# Main.net
KiCad netlist of a schematic drawn in Altium Designer
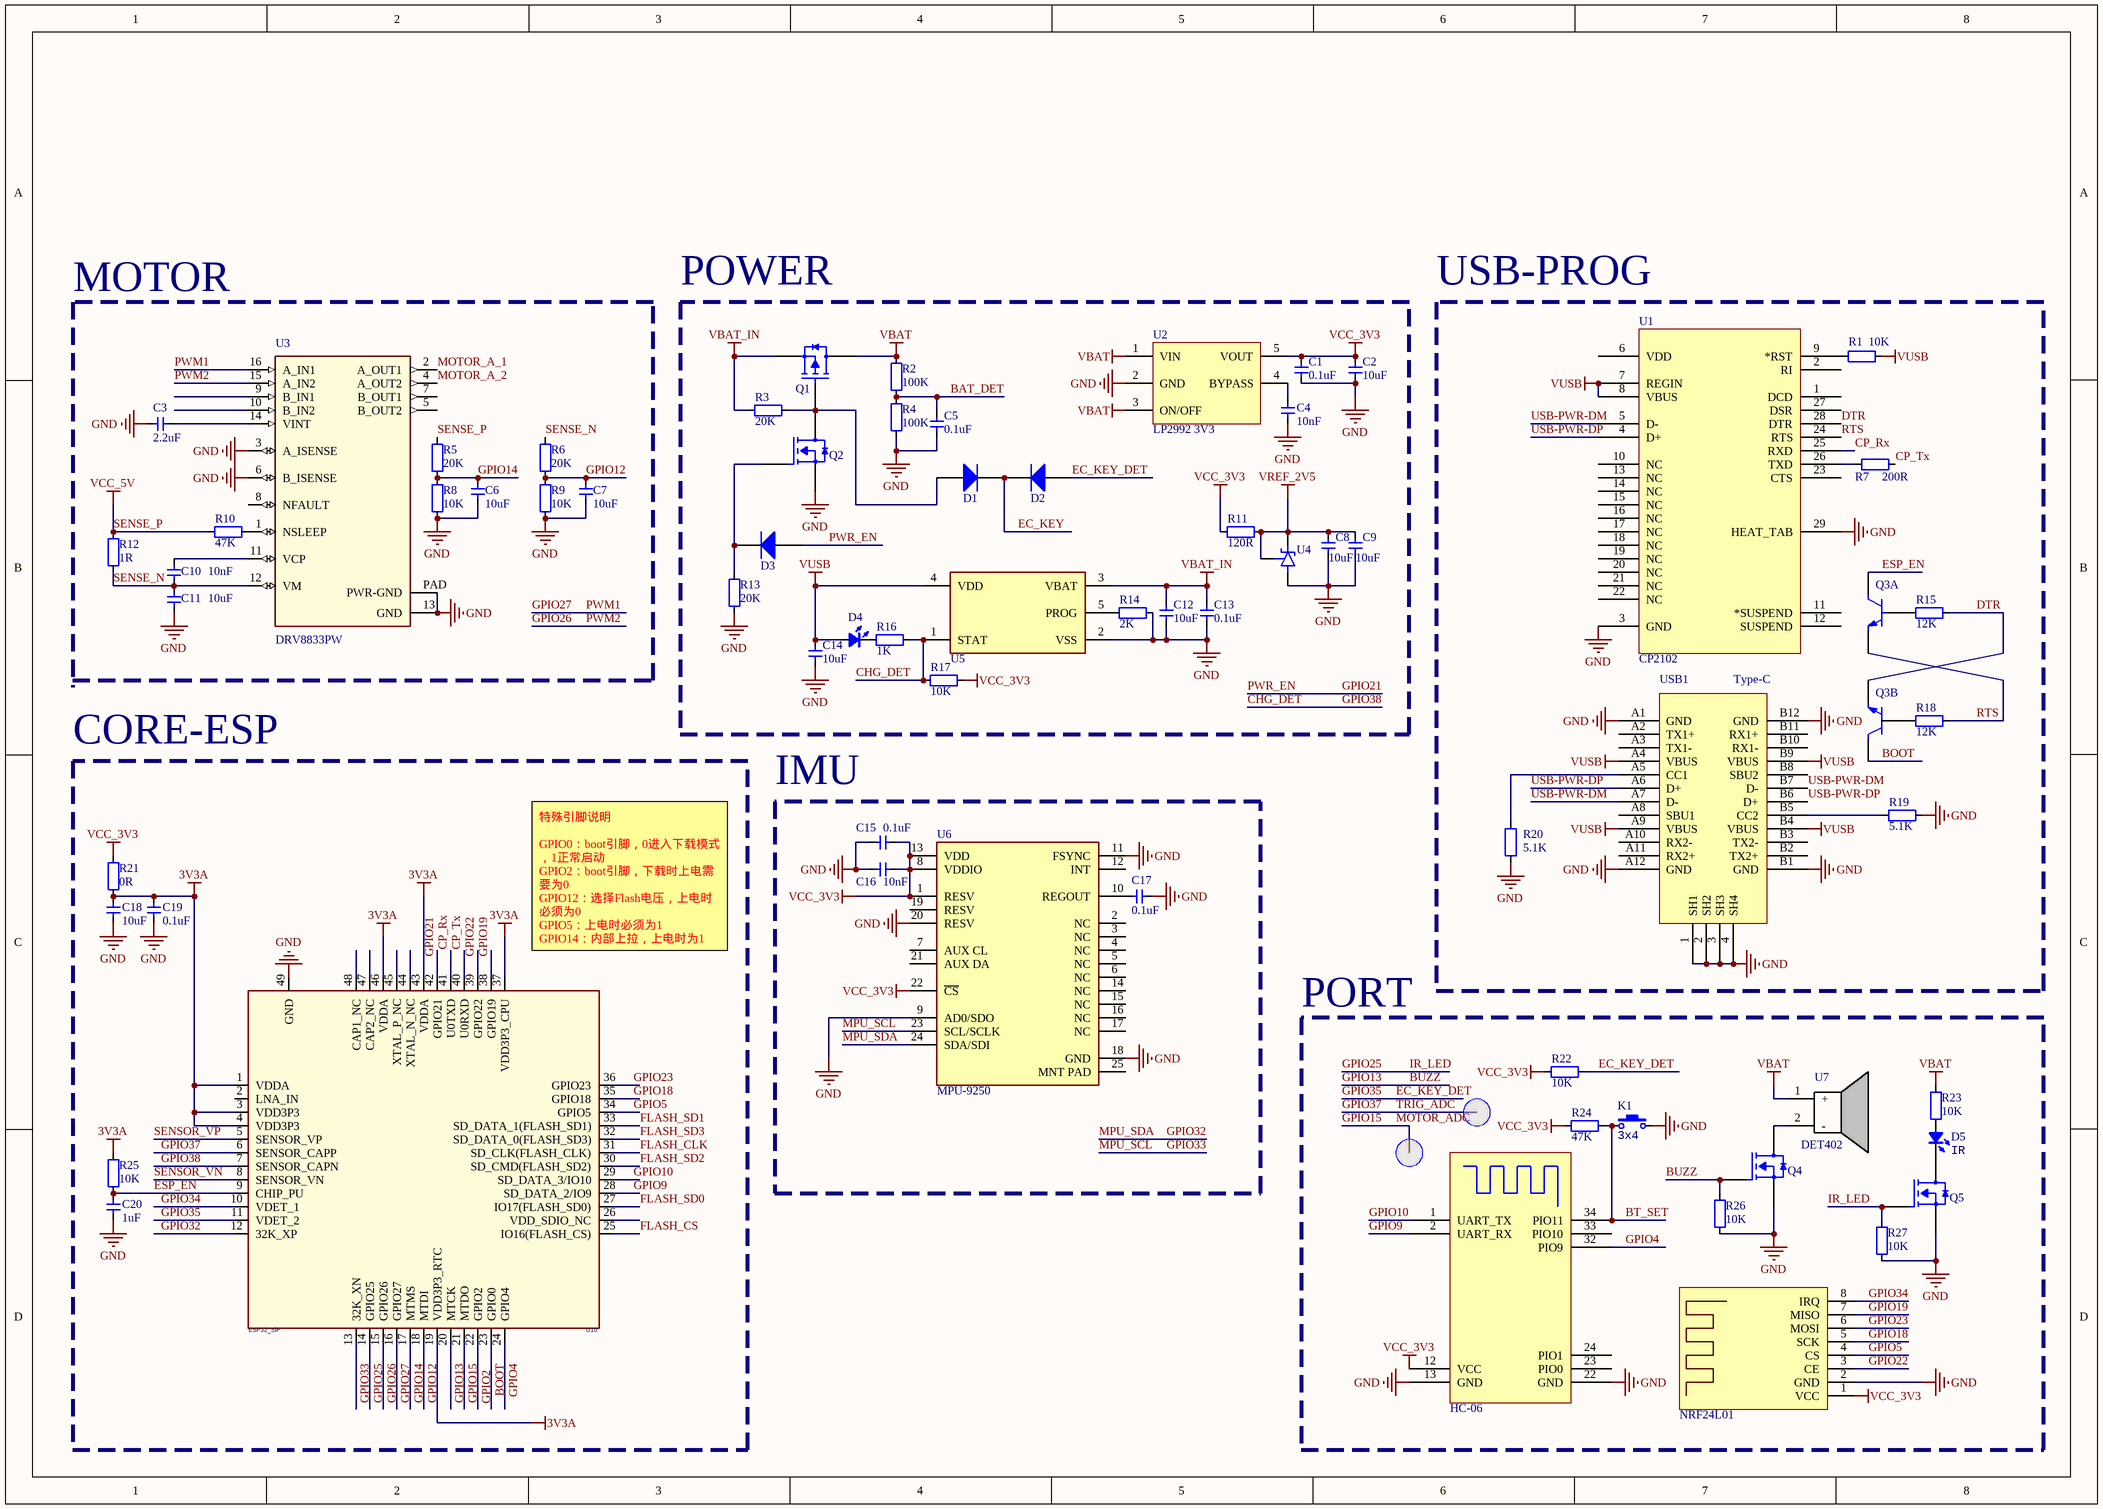
[diagram p0: Main.SchDoc]

(export (version "E")
  (design (tool "Eeschema 10.0.6"))
  (components
    (comp (ref "C1")
      (value "0.1uF")
      (footprint "CAP_0402")
      (description "Capacitor")
      (libsource (lib "MyPcbLib") (part "电容-0402"))
    )
    (comp (ref "C2")
      (value "10uF")
      (footprint "CAP_0402")
      (description "Capacitor")
      (libsource (lib "MyPcbLib") (part "电容-0402"))
    )
    (comp (ref "C3")
      (value "2.2uF")
      (footprint "CAP_0402")
      (description "Capacitor")
      (libsource (lib "MyPcbLib") (part "电容-0402"))
    )
    (comp (ref "C4")
      (value "10nF")
      (footprint "CAP_0402")
      (description "Capacitor")
      (libsource (lib "MyPcbLib") (part "电容-0402"))
    )
    (comp (ref "C5")
      (value "0.1uF")
      (footprint "CAP_0402")
      (description "Capacitor")
      (libsource (lib "MyPcbLib") (part "电容-0402"))
    )
    (comp (ref "C6")
      (value "10uF")
      (footprint "CAP_0402")
      (description "Capacitor")
      (libsource (lib "MyPcbLib") (part "电容-0402"))
    )
    (comp (ref "C7")
      (value "10uF")
      (footprint "CAP_0402")
      (description "Capacitor")
      (libsource (lib "MyPcbLib") (part "电容-0402"))
    )
    (comp (ref "C8")
      (value "10uF")
      (footprint "CAP_0402")
      (description "Capacitor")
      (libsource (lib "MyPcbLib") (part "电容-0402"))
    )
    (comp (ref "C9")
      (value "10uF")
      (footprint "CAP_0402")
      (description "Capacitor")
      (libsource (lib "MyPcbLib") (part "电容-0402"))
    )
    (comp (ref "C10")
      (value "10nF")
      (footprint "CAP_0402")
      (description "Capacitor")
      (libsource (lib "MyPcbLib") (part "电容-0402"))
    )
    (comp (ref "C11")
      (value "10uF")
      (footprint "CAP_0402")
      (description "Capacitor")
      (libsource (lib "MyPcbLib") (part "电容-0402"))
    )
    (comp (ref "C12")
      (value "10uF")
      (footprint "CAP_0402")
      (description "Capacitor")
      (libsource (lib "MyPcbLib") (part "电容-0402"))
    )
    (comp (ref "C13")
      (value "0.1uF")
      (footprint "CAP_0402")
      (description "Capacitor")
      (libsource (lib "MyPcbLib") (part "电容-0402"))
    )
    (comp (ref "C14")
      (value "10uF")
      (footprint "CAP_0402")
      (description "Capacitor")
      (libsource (lib "MyPcbLib") (part "电容-0402"))
    )
    (comp (ref "C15")
      (value "0.1uF")
      (footprint "CAP_0402")
      (description "Capacitor")
      (libsource (lib "MyPcbLib") (part "电容-0402"))
    )
    (comp (ref "C16")
      (value "10nF")
      (footprint "CAP_0402")
      (description "Capacitor")
      (libsource (lib "MyPcbLib") (part "电容-0402"))
    )
    (comp (ref "C17")
      (value "0.1uF")
      (footprint "CAP_0402")
      (description "Capacitor")
      (libsource (lib "MyPcbLib") (part "电容-0402"))
    )
    (comp (ref "C18")
      (value "10uF")
      (footprint "CAP_0402")
      (description "Capacitor")
      (libsource (lib "MyPcbLib") (part "电容-0402"))
    )
    (comp (ref "C19")
      (value "0.1uF")
      (footprint "CAP_0402")
      (description "Capacitor")
      (libsource (lib "MyPcbLib") (part "电容-0402"))
    )
    (comp (ref "C20")
      (value "1uF")
      (footprint "CAP_0402")
      (description "Capacitor")
      (libsource (lib "MyPcbLib") (part "电容-0402"))
    )
    (comp (ref "D1")
      (value "二极管-5819W")
      (footprint "SOD-323")
      (description "40V")
      (libsource (lib "MyPcbLib") (part "二极管-5819W"))
    )
    (comp (ref "D2")
      (value "二极管-5819W")
      (footprint "SOD-323")
      (description "40V")
      (libsource (lib "MyPcbLib") (part "二极管-5819W"))
    )
    (comp (ref "D3")
      (value "二极管-5819W")
      (footprint "SOD-323")
      (description "40V")
      (libsource (lib "MyPcbLib") (part "二极管-5819W"))
    )
    (comp (ref "D4")
      (value "color?")
      (footprint "LED_0402_RED")
      (description "LED")
      (libsource (lib "KitSprout") (part "LED_0402"))
    )
    (comp (ref "D5")
      (value "color?")
      (footprint "LED_0805_RED")
      (description "LED")
      (fields (field (name "TYPE") "IR"))
      (libsource (lib "KitSprout") (part "LED_0805"))
    )
    (comp (ref "K1")
      (value "3x4")
      (footprint "ButtonTACT_3x4x2_180")
      (description "Button")
      (fields (field (name "Comment") "TACT 2P"))
      (libsource (lib "KitSprout") (part "ButtonTACT_3x4x2_180"))
    )
    (comp (ref "Q1")
      (value "AO3401A")
      (footprint "SOT23-3")
      (description "P-MOS")
      (libsource (lib "MyPcbLib") (part "AO3401A"))
    )
    (comp (ref "Q2")
      (value "AO3400A")
      (footprint "SOT23-3")
      (description "N-MOS")
      (libsource (lib "MyPcbLib") (part "AO3400A"))
    )
    (comp (ref "Q3")
      (value "BC847BVC-7")
      (footprint "SOT563-6")
      (libsource (lib "MyPcbLib") (part "BC847BVC-7"))
    )
    (comp (ref "Q4")
      (value "AO3400A")
      (footprint "SOT23-3")
      (description "N-MOS")
      (libsource (lib "MyPcbLib") (part "AO3400A"))
    )
    (comp (ref "Q5")
      (value "AO3400A")
      (footprint "SOT23-3")
      (description "N-MOS")
      (libsource (lib "MyPcbLib") (part "AO3400A"))
    )
    (comp (ref "R1")
      (value "10K")
      (footprint "RES_0402")
      (description "Resistor")
      (libsource (lib "") (part "电阻-0402_3"))
    )
    (comp (ref "R2")
      (value "100K")
      (footprint "RES_0402")
      (description "Resistor")
      (libsource (lib "MyPcbLib") (part "电阻-0402"))
    )
    (comp (ref "R3")
      (value "20K")
      (footprint "RES_0402")
      (description "Resistor")
      (libsource (lib "") (part "电阻-0402_1"))
    )
    (comp (ref "R4")
      (value "100K")
      (footprint "RES_0402")
      (description "Resistor")
      (libsource (lib "MyPcbLib") (part "电阻-0402"))
    )
    (comp (ref "R5")
      (value "20K")
      (footprint "RES_0402")
      (description "Resistor")
      (libsource (lib "MyPcbLib") (part "电阻-0402"))
    )
    (comp (ref "R6")
      (value "20K")
      (footprint "RES_0402")
      (description "Resistor")
      (libsource (lib "MyPcbLib") (part "电阻-0402"))
    )
    (comp (ref "R7")
      (value "200R")
      (footprint "RES_0402")
      (description "Resistor")
      (libsource (lib "") (part "电阻-0402_3"))
    )
    (comp (ref "R8")
      (value "10K")
      (footprint "RES_0402")
      (description "Resistor")
      (libsource (lib "MyPcbLib") (part "电阻-0402"))
    )
    (comp (ref "R9")
      (value "10K")
      (footprint "RES_0402")
      (description "Resistor")
      (libsource (lib "MyPcbLib") (part "电阻-0402"))
    )
    (comp (ref "R10")
      (value "47K")
      (footprint "RES_0402")
      (description "Resistor")
      (libsource (lib "") (part "电阻-0402_3"))
    )
    (comp (ref "R11")
      (value "120R")
      (footprint "RES_0402")
      (description "Resistor")
      (libsource (lib "") (part "电阻-0402_1"))
    )
    (comp (ref "R12")
      (value "1R")
      (footprint "1206-RES")
      (description "Resistor")
      (libsource (lib "MyPcbLib") (part "电阻-1206"))
    )
    (comp (ref "R13")
      (value "20K")
      (footprint "RES_0402")
      (description "Resistor")
      (libsource (lib "MyPcbLib") (part "电阻-0402"))
    )
    (comp (ref "R14")
      (value "2K")
      (footprint "RES_0402")
      (description "Resistor")
      (libsource (lib "") (part "电阻-0402_1"))
    )
    (comp (ref "R15")
      (value "12K")
      (footprint "RES_0402")
      (description "Resistor")
      (libsource (lib "") (part "电阻-0402_3"))
    )
    (comp (ref "R16")
      (value "1K")
      (footprint "RES_0402")
      (description "Resistor")
      (libsource (lib "") (part "电阻-0402_1"))
    )
    (comp (ref "R17")
      (value "10K")
      (footprint "RES_0402")
      (description "Resistor")
      (libsource (lib "") (part "电阻-0402_1"))
    )
    (comp (ref "R18")
      (value "12K")
      (footprint "RES_0402")
      (description "Resistor")
      (libsource (lib "") (part "电阻-0402_3"))
    )
    (comp (ref "R19")
      (value "5.1K")
      (footprint "RES_0402")
      (description "Resistor")
      (libsource (lib "") (part "电阻-0402_3"))
    )
    (comp (ref "R20")
      (value "5.1K")
      (footprint "RES_0402")
      (description "Resistor")
      (libsource (lib "") (part "电阻-0402_2"))
    )
    (comp (ref "R21")
      (value "0R")
      (footprint "RES_0402")
      (description "Resistor")
      (libsource (lib "") (part "电阻-0402_2"))
    )
    (comp (ref "R22")
      (value "10K")
      (footprint "RES_0402")
      (description "Resistor")
      (libsource (lib "") (part "电阻-0402_1"))
    )
    (comp (ref "R23")
      (value "10K")
      (footprint "RES_0402")
      (description "Resistor")
      (libsource (lib "MyPcbLib") (part "电阻-0402"))
    )
    (comp (ref "R24")
      (value "47K")
      (footprint "RES_0402")
      (description "Resistor")
      (libsource (lib "") (part "电阻-0402_1"))
    )
    (comp (ref "R25")
      (value "10K")
      (footprint "RES_0402")
      (description "Resistor")
      (libsource (lib "") (part "电阻-0402_2"))
    )
    (comp (ref "R26")
      (value "10K")
      (footprint "RES_0402")
      (description "Resistor")
      (libsource (lib "MyPcbLib") (part "电阻-0402"))
    )
    (comp (ref "R27")
      (value "10K")
      (footprint "RES_0402")
      (description "Resistor")
      (libsource (lib "MyPcbLib") (part "电阻-0402"))
    )
    (comp (ref "T1") (value "测试点") (footprint "TEST_PT") (libsource (lib "MyPcbLib") (part "测试点")))
    (comp (ref "T2") (value "测试点") (footprint "TEST_PT") (libsource (lib "MyPcbLib") (part "测试点")))
    (comp (ref "U1")
      (value "CP2102")
      (footprint "QFN-28")
      (description "USB转TTL")
      (libsource (lib "mLib") (part "CP2102"))
    )
    (comp (ref "U2")
      (value "LP2992 3V3")
      (footprint "SOT23-5")
      (description "LDO")
      (libsource (lib "mLib") (part "LP2992"))
    )
    (comp (ref "U3") (value "DRV8833PW") (footprint "TSSOP-16") (libsource (lib "mLib") (part "DRV8833PW")))
    (comp (ref "U4")
      (value "TL431IDBZT")
      (footprint "SOT23-3")
      (description "Adjustable precision shunt regulator 3-SOT-23 -40 to 85")
      (fields (field (name "MF") "Texas Instruments"))
      (libsource (lib "MyPcbLib") (part "TL431IDBZT"))
    )
    (comp (ref "U5")
      (value "MCP73831T")
      (footprint "SOT23-5")
      (libsource (lib "MyPcbLib") (part "MCP73831T"))
    )
    (comp (ref "U6")
      (value "MPU9250")
      (footprint "QFN-24-3x3")
      (description "IC IMU ACCEL/GYRO/MAG I2C/SPI 24QFN")
      (fields
        (field (name "MANUFACTURER") "TDK InvenSense")
        (field (name "MOUSER PART NUMBER") "410-MPU-9250")
        (field (name "PART NUMBER") "MPU-9250")
      )
      (libsource (lib "MyPcbLib") (part "MPU9250"))
    )
    (comp (ref "U7") (value "DET402") (footprint "DET402") (libsource (lib "MyPcbLib") (part "DET402")))
    (comp (ref "U8") (value "HC-06") (footprint "蓝牙模块HC-06") (libsource (lib "MyPcbLib") (part "蓝牙模块HC-06")))
    (comp (ref "U9")
      (value "NRF24L01")
      (footprint "NRF24L01-MODULE")
      (libsource (lib "MyPcbLib") (part "NRF24L01模块"))
    )
    (comp (ref "U10")
      (value "ESP32_SIP")
      (footprint "QFN-48_7X7")
      (libsource (lib "mLib") (part "ESP32-PICO"))
    )
    (comp (ref "USB1")
      (value "Type-C")
      (footprint "Type-C-TOP")
      (libsource (lib "MyPcbLib") (part "USB-Type-C-TOP"))
    )
  )
  (nets
    (net (code "1") (name "/BAT_DET") (class "Default")
      (node (ref "C5") (pin "2") (pinfunction "2_2") (pintype "passive"))
      (node (ref "R2") (pin "1") (pinfunction "1_1") (pintype "passive"))
      (node (ref "R4") (pin "2") (pinfunction "2_2") (pintype "passive"))
    )
    (net (code "2") (name "/BOOT") (class "Default")
      (node (ref "Q3") (pin "3") (pinfunction "C2_3") (pintype "passive"))
      (node (ref "U10") (pin "23") (pinfunction "GPIO0_23") (pintype "passive"))
    )
    (net (code "3") (name "/BT_SET") (class "Default")
      (node (ref "K1") (pin "1") (pinfunction "1_1") (pintype "passive"))
      (node (ref "R24") (pin "2") (pinfunction "2_2") (pintype "passive"))
      (node (ref "U8") (pin "34") (pinfunction "PIO11_34") (pintype "passive"))
    )
    (net (code "4") (name "/BUZZ") (class "Default")
      (node (ref "Q4") (pin "1") (pinfunction "G_1") (pintype "passive"))
      (node (ref "R26") (pin "2") (pinfunction "2_2") (pintype "passive"))
      (node (ref "U10") (pin "20") (pinfunction "MTCK_20") (pintype "passive"))
    )
    (net (code "5") (name "/CHG_DET") (class "Default")
      (node (ref "R16") (pin "2") (pinfunction "2_2") (pintype "passive"))
      (node (ref "R17") (pin "1") (pinfunction "1_1") (pintype "passive"))
      (node (ref "U10") (pin "7") (pinfunction "SENSOR_CAPN_7") (pintype "passive"))
      (node (ref "U5") (pin "1") (pinfunction "STAT_1") (pintype "passive"))
    )
    (net (code "6") (name "/CP_Rx") (class "Default")
      (node (ref "U1") (pin "25") (pinfunction "RXD_25") (pintype "passive"))
      (node (ref "U10") (pin "41") (pinfunction "U0TXD_41") (pintype "power_in"))
    )
    (net (code "7") (name "/CP_Tx") (class "Default")
      (node (ref "R7") (pin "1") (pinfunction "1_1") (pintype "passive"))
      (node (ref "U10") (pin "40") (pinfunction "U0RXD_40") (pintype "power_in"))
    )
    (net (code "8") (name "/DTR") (class "Default")
      (node (ref "Q3") (pin "4") (pinfunction "E2_4") (pintype "passive"))
      (node (ref "R15") (pin "1") (pinfunction "1_1") (pintype "passive"))
      (node (ref "U1") (pin "28") (pinfunction "DTR_28") (pintype "passive"))
    )
    (net (code "9") (name "/EC_KEY") (class "Default")
      (node (ref "D1") (pin "2") (pinfunction "K_2") (pintype "passive"))
      (node (ref "D2") (pin "2") (pinfunction "K_2") (pintype "passive"))
    )
    (net (code "10") (name "/EC_KEY_DET") (class "Default")
      (node (ref "D2") (pin "1") (pinfunction "A_1") (pintype "passive"))
      (node (ref "R22") (pin "2") (pinfunction "2_2") (pintype "passive"))
      (node (ref "U10") (pin "11") (pinfunction "VDET_2_11") (pintype "passive"))
    )
    (net (code "11") (name "/ESP_EN") (class "Default")
      (node (ref "C20") (pin "1") (pinfunction "1_1") (pintype "passive"))
      (node (ref "Q3") (pin "6") (pinfunction "C1_6") (pintype "passive"))
      (node (ref "R25") (pin "2") (pinfunction "2_2") (pintype "passive"))
      (node (ref "U10") (pin "9") (pinfunction "CHIP_PU_9") (pintype "passive"))
    )
    (net (code "12") (name "/FLASH_CLK") (class "Default")
      (node (ref "U10") (pin "31") (pinfunction "SD_CLK(FLASH_CLK)_31") (pintype "passive"))
    )
    (net (code "13") (name "/FLASH_CS") (class "Default")
      (node (ref "U10") (pin "25") (pinfunction "IO16(FLASH_CS)_25") (pintype "passive"))
    )
    (net (code "14") (name "/FLASH_SD0") (class "Default")
      (node (ref "U10") (pin "27") (pinfunction "IO17(FLASH_SD0)_27") (pintype "passive"))
    )
    (net (code "15") (name "/FLASH_SD1") (class "Default")
      (node (ref "U10") (pin "33") (pinfunction "SD_DATA_1(FLASH_SD1)_33") (pintype "passive"))
    )
    (net (code "16") (name "/FLASH_SD2") (class "Default")
      (node (ref "U10") (pin "30") (pinfunction "SD_CMD(FLASH_SD2)_30") (pintype "passive"))
    )
    (net (code "17") (name "/FLASH_SD3") (class "Default")
      (node (ref "U10") (pin "32") (pinfunction "SD_DATA_0(FLASH_SD3)_32") (pintype "passive"))
    )
    (net (code "18") (name "/GPIO2") (class "Default")
      (node (ref "U10") (pin "22") (pinfunction "GPIO2_22") (pintype "passive"))
    )
    (net (code "19") (name "/GPIO4") (class "Default")
      (node (ref "U10") (pin "24") (pinfunction "GPIO4_24") (pintype "passive"))
      (node (ref "U8") (pin "32") (pinfunction "PIO9_32") (pintype "passive"))
    )
    (net (code "20") (name "/GPIO5") (class "Default")
      (node (ref "U10") (pin "34") (pinfunction "GPIO5_34") (pintype "passive"))
      (node (ref "U9") (pin "4") (pinfunction "CS_4") (pintype "passive"))
    )
    (net (code "21") (name "/GPIO9") (class "Default")
      (node (ref "U10") (pin "28") (pinfunction "SD_DATA_2/IO9_28") (pintype "passive"))
      (node (ref "U8") (pin "2") (pinfunction "UART_RX_2") (pintype "passive"))
    )
    (net (code "22") (name "/GPIO10") (class "Default")
      (node (ref "U10") (pin "29") (pinfunction "SD_DATA_3/IO10_29") (pintype "passive"))
      (node (ref "U8") (pin "1") (pinfunction "UART_TX_1") (pintype "passive"))
    )
    (net (code "23") (name "/GPIO12") (class "Default")
      (node (ref "C7") (pin "2") (pinfunction "2_2") (pintype "passive"))
      (node (ref "R6") (pin "1") (pinfunction "1_1") (pintype "passive"))
      (node (ref "R9") (pin "2") (pinfunction "2_2") (pintype "passive"))
      (node (ref "U10") (pin "18") (pinfunction "MTDI_18") (pintype "passive"))
    )
    (net (code "24") (name "/GPIO14") (class "Default")
      (node (ref "C6") (pin "2") (pinfunction "2_2") (pintype "passive"))
      (node (ref "R5") (pin "1") (pinfunction "1_1") (pintype "passive"))
      (node (ref "R8") (pin "2") (pinfunction "2_2") (pintype "passive"))
      (node (ref "U10") (pin "17") (pinfunction "MTMS_17") (pintype "passive"))
    )
    (net (code "25") (name "/GPIO15") (class "Default")
      (node (ref "T2") (pin "0") (pinfunction "0_0") (pintype "passive"))
      (node (ref "U10") (pin "21") (pinfunction "MTDO_21") (pintype "passive"))
    )
    (net (code "26") (name "/GPIO18") (class "Default")
      (node (ref "U10") (pin "35") (pinfunction "GPIO18_35") (pintype "passive"))
      (node (ref "U9") (pin "5") (pinfunction "SCK_5") (pintype "passive"))
    )
    (net (code "27") (name "/GPIO19") (class "Default")
      (node (ref "U10") (pin "38") (pinfunction "GPIO19_38") (pintype "passive"))
      (node (ref "U9") (pin "7") (pinfunction "MISO_7") (pintype "passive"))
    )
    (net (code "28") (name "/GPIO21") (class "Default")
      (node (ref "D3") (pin "1") (pinfunction "A_1") (pintype "passive"))
      (node (ref "U10") (pin "42") (pinfunction "GPIO21_42") (pintype "passive"))
    )
    (net (code "29") (name "/GPIO22") (class "Default")
      (node (ref "U10") (pin "39") (pinfunction "GPIO22_39") (pintype "passive"))
      (node (ref "U9") (pin "3") (pinfunction "CE_3") (pintype "passive"))
    )
    (net (code "30") (name "/GPIO23") (class "Default")
      (node (ref "U10") (pin "36") (pinfunction "GPIO23_36") (pintype "passive"))
      (node (ref "U9") (pin "6") (pinfunction "MOSI_6") (pintype "passive"))
    )
    (net (code "31") (name "/GPIO25") (class "Default")
      (node (ref "Q5") (pin "1") (pinfunction "G_1") (pintype "passive"))
      (node (ref "R27") (pin "2") (pinfunction "2_2") (pintype "passive"))
      (node (ref "U10") (pin "14") (pinfunction "GPIO25_14") (pintype "passive"))
    )
    (net (code "32") (name "/GPIO26") (class "Default")
      (node (ref "U10") (pin "15") (pinfunction "GPIO26_15") (pintype "passive"))
      (node (ref "U3") (pin "15") (pinfunction "A_IN2_15") (pintype "input"))
    )
    (net (code "33") (name "/GPIO27") (class "Default")
      (node (ref "U10") (pin "16") (pinfunction "GPIO27_16") (pintype "passive"))
      (node (ref "U3") (pin "16") (pinfunction "A_IN1_16") (pintype "input"))
    )
    (net (code "34") (name "/GPIO32") (class "Default")
      (node (ref "U10") (pin "12") (pinfunction "32K_XP_12") (pintype "passive"))
      (node (ref "U6") (pin "24") (pinfunction "SDA/SDI_24") (pintype "passive"))
    )
    (net (code "35") (name "/GPIO33") (class "Default")
      (node (ref "U10") (pin "13") (pinfunction "32K_XN_13") (pintype "passive"))
      (node (ref "U6") (pin "23") (pinfunction "SCL/SCLK_23") (pintype "passive"))
    )
    (net (code "36") (name "/GPIO34") (class "Default")
      (node (ref "U10") (pin "10") (pinfunction "VDET_1_10") (pintype "passive"))
      (node (ref "U9") (pin "8") (pinfunction "IRQ_8") (pintype "passive"))
    )
    (net (code "37") (name "/GPIO37") (class "Default")
      (node (ref "T1") (pin "0") (pinfunction "0_0") (pintype "passive"))
      (node (ref "U10") (pin "6") (pinfunction "SENSOR_CAPP_6") (pintype "passive"))
    )
    (net (code "38") (name "/MOTOR_A_1") (class "Default")
      (node (ref "U3") (pin "2") (pinfunction "A_OUT1_2") (pintype "output"))
    )
    (net (code "39") (name "/MOTOR_A_2") (class "Default")
      (node (ref "U3") (pin "4") (pinfunction "A_OUT2_4") (pintype "output"))
    )
    (net (code "40") (name "/RTS") (class "Default")
      (node (ref "Q3") (pin "1") (pinfunction "E1_1") (pintype "passive"))
      (node (ref "R18") (pin "1") (pinfunction "1_1") (pintype "passive"))
      (node (ref "U1") (pin "24") (pinfunction "RTS_24") (pintype "passive"))
    )
    (net (code "41") (name "/SENSE_N") (class "Default")
      (node (ref "C10") (pin "1") (pinfunction "1_1") (pintype "passive"))
      (node (ref "C11") (pin "2") (pinfunction "2_2") (pintype "passive"))
      (node (ref "R12") (pin "1") (pinfunction "1_1") (pintype "passive"))
      (node (ref "R6") (pin "2") (pinfunction "2_2") (pintype "passive"))
      (node (ref "U3") (pin "12") (pinfunction "VM_12") (pintype "bidirectional"))
    )
    (net (code "42") (name "/SENSOR_VN") (class "Default")
      (node (ref "U10") (pin "8") (pinfunction "SENSOR_VN_8") (pintype "passive"))
    )
    (net (code "43") (name "/SENSOR_VP") (class "Default")
      (node (ref "U10") (pin "5") (pinfunction "SENSOR_VP_5") (pintype "passive"))
    )
    (net (code "44") (name "/USB-PWR-DM") (class "Default")
      (node (ref "U1") (pin "5") (pinfunction "D-_5") (pintype "passive"))
      (node (ref "USB1") (pin "A7") (pinfunction "D-_A7") (pintype "passive"))
      (node (ref "USB1") (pin "B7") (pinfunction "D-_B7") (pintype "passive"))
    )
    (net (code "45") (name "/USB-PWR-DP") (class "Default")
      (node (ref "U1") (pin "4") (pinfunction "D+_4") (pintype "passive"))
      (node (ref "USB1") (pin "A6") (pinfunction "D+_A6") (pintype "passive"))
      (node (ref "USB1") (pin "B6") (pinfunction "D+_B6") (pintype "passive"))
    )
    (net (code "46") (name "3V3A") (class "Default")
      (node (ref "C18") (pin "2") (pinfunction "2_2") (pintype "passive"))
      (node (ref "C19") (pin "2") (pinfunction "2_2") (pintype "passive"))
      (node (ref "R21") (pin "2") (pinfunction "2_2") (pintype "passive"))
      (node (ref "R25") (pin "1") (pinfunction "1_1") (pintype "passive"))
      (node (ref "U10") (pin "1") (pinfunction "VDDA_1") (pintype "power_in"))
      (node (ref "U10") (pin "19") (pinfunction "VDD3P3_RTC_19") (pintype "power_in"))
      (node (ref "U10") (pin "3") (pinfunction "VDD3P3_3") (pintype "power_in"))
      (node (ref "U10") (pin "37") (pinfunction "VDD3P3_CPU_37") (pintype "power_in"))
      (node (ref "U10") (pin "4") (pinfunction "VDD3P3_4") (pintype "power_in"))
      (node (ref "U10") (pin "43") (pinfunction "VDDA_43") (pintype "power_in"))
      (node (ref "U10") (pin "46") (pinfunction "VDDA_46") (pintype "power_in"))
    )
    (net (code "47") (name "GND") (class "Default")
      (node (ref "C1") (pin "1") (pinfunction "1_1") (pintype "passive"))
      (node (ref "C11") (pin "1") (pinfunction "1_1") (pintype "passive"))
      (node (ref "C12") (pin "1") (pinfunction "1_1") (pintype "passive"))
      (node (ref "C13") (pin "1") (pinfunction "1_1") (pintype "passive"))
      (node (ref "C14") (pin "1") (pinfunction "1_1") (pintype "passive"))
      (node (ref "C15") (pin "2") (pinfunction "2_2") (pintype "passive"))
      (node (ref "C16") (pin "2") (pinfunction "2_2") (pintype "passive"))
      (node (ref "C17") (pin "1") (pinfunction "1_1") (pintype "passive"))
      (node (ref "C18") (pin "1") (pinfunction "1_1") (pintype "passive"))
      (node (ref "C19") (pin "1") (pinfunction "1_1") (pintype "passive"))
      (node (ref "C2") (pin "1") (pinfunction "1_1") (pintype "passive"))
      (node (ref "C20") (pin "2") (pinfunction "2_2") (pintype "passive"))
      (node (ref "C3") (pin "1") (pinfunction "1_1") (pintype "passive"))
      (node (ref "C4") (pin "1") (pinfunction "1_1") (pintype "passive"))
      (node (ref "C5") (pin "1") (pinfunction "1_1") (pintype "passive"))
      (node (ref "C6") (pin "1") (pinfunction "1_1") (pintype "passive"))
      (node (ref "C7") (pin "1") (pinfunction "1_1") (pintype "passive"))
      (node (ref "C8") (pin "1") (pinfunction "1_1") (pintype "passive"))
      (node (ref "C9") (pin "1") (pinfunction "1_1") (pintype "passive"))
      (node (ref "K1") (pin "2") (pinfunction "2_2") (pintype "passive"))
      (node (ref "Q2") (pin "2") (pinfunction "S_2") (pintype "passive"))
      (node (ref "Q4") (pin "2") (pinfunction "S_2") (pintype "passive"))
      (node (ref "Q5") (pin "2") (pinfunction "S_2") (pintype "passive"))
      (node (ref "R13") (pin "1") (pinfunction "1_1") (pintype "passive"))
      (node (ref "R14") (pin "2") (pinfunction "2_2") (pintype "passive"))
      (node (ref "R19") (pin "1") (pinfunction "1_1") (pintype "passive"))
      (node (ref "R20") (pin "2") (pinfunction "2_2") (pintype "passive"))
      (node (ref "R26") (pin "1") (pinfunction "1_1") (pintype "passive"))
      (node (ref "R27") (pin "1") (pinfunction "1_1") (pintype "passive"))
      (node (ref "R4") (pin "1") (pinfunction "1_1") (pintype "passive"))
      (node (ref "R8") (pin "1") (pinfunction "1_1") (pintype "passive"))
      (node (ref "R9") (pin "1") (pinfunction "1_1") (pintype "passive"))
      (node (ref "U1") (pin "29") (pinfunction "HEAT_TAB_29") (pintype "passive"))
      (node (ref "U1") (pin "3") (pinfunction "GND_3") (pintype "passive"))
      (node (ref "U10") (pin "49") (pinfunction "GND_49") (pintype "power_in"))
      (node (ref "U2") (pin "2") (pinfunction "GND_2") (pintype "passive"))
      (node (ref "U3") (pin "13") (pinfunction "GND_13") (pintype "power_in"))
      (node (ref "U3") (pin "3") (pinfunction "A_ISENSE_3") (pintype "bidirectional"))
      (node (ref "U3") (pin "6") (pinfunction "B_ISENSE_6") (pintype "bidirectional"))
      (node (ref "U3") (pin "PAD") (pinfunction "PWR-GND_PAD") (pintype "power_in"))
      (node (ref "U4") (pin "3") (pinfunction "ANODE_3") (pintype "passive"))
      (node (ref "U5") (pin "2") (pinfunction "VSS_2") (pintype "power_in"))
      (node (ref "U6") (pin "11") (pinfunction "FSYNC_11") (pintype "passive"))
      (node (ref "U6") (pin "18") (pinfunction "GND_18") (pintype "passive"))
      (node (ref "U6") (pin "20") (pinfunction "RESV_20") (pintype "passive"))
      (node (ref "U6") (pin "9") (pinfunction "AD0/SDO_9") (pintype "passive"))
      (node (ref "U8") (pin "13") (pinfunction "GND_13") (pintype "passive"))
      (node (ref "U8") (pin "22") (pinfunction "GND_22") (pintype "passive"))
      (node (ref "U9") (pin "2") (pinfunction "GND_2") (pintype "passive"))
      (node (ref "USB1") (pin "1") (pinfunction "SH1_1") (pintype "passive"))
      (node (ref "USB1") (pin "2") (pinfunction "SH2_2") (pintype "passive"))
      (node (ref "USB1") (pin "3") (pinfunction "SH3_3") (pintype "passive"))
      (node (ref "USB1") (pin "4") (pinfunction "SH4_4") (pintype "passive"))
      (node (ref "USB1") (pin "A1") (pinfunction "GND_A1") (pintype "passive"))
      (node (ref "USB1") (pin "A12") (pinfunction "GND_A12") (pintype "passive"))
      (node (ref "USB1") (pin "B1") (pinfunction "GND_B1") (pintype "passive"))
      (node (ref "USB1") (pin "B12") (pinfunction "GND_B12") (pintype "passive"))
    )
    (net (code "48") (name "Net-(D1-A)") (class "Default")
      (node (ref "D1") (pin "1") (pinfunction "A_1") (pintype "passive"))
      (node (ref "Q1") (pin "1") (pinfunction "G_1") (pintype "passive"))
      (node (ref "Q2") (pin "3") (pinfunction "D_3") (pintype "passive"))
      (node (ref "R3") (pin "2") (pinfunction "2_2") (pintype "passive"))
    )
    (net (code "49") (name "Net-(D3-K)") (class "Default")
      (node (ref "D3") (pin "2") (pinfunction "K_2") (pintype "passive"))
      (node (ref "Q2") (pin "1") (pinfunction "G_1") (pintype "passive"))
      (node (ref "R13") (pin "2") (pinfunction "2_2") (pintype "passive"))
    )
    (net (code "50") (name "Net-(D4-K)") (class "Default")
      (node (ref "D4") (pin "2") (pinfunction "K_2") (pintype "passive"))
      (node (ref "R16") (pin "1") (pinfunction "1_1") (pintype "passive"))
    )
    (net (code "51") (name "Net-(D5-A)") (class "Default")
      (node (ref "D5") (pin "1") (pinfunction "A_1") (pintype "passive"))
      (node (ref "R23") (pin "1") (pinfunction "1_1") (pintype "passive"))
    )
    (net (code "52") (name "Net-(D5-K)") (class "Default")
      (node (ref "D5") (pin "2") (pinfunction "K_2") (pintype "passive"))
      (node (ref "Q5") (pin "3") (pinfunction "D_3") (pintype "passive"))
    )
    (net (code "53") (name "Net-(Q3A-B1)") (class "Default")
      (node (ref "Q3") (pin "2") (pinfunction "B1_2") (pintype "passive"))
      (node (ref "R15") (pin "2") (pinfunction "2_2") (pintype "passive"))
    )
    (net (code "54") (name "Net-(Q3B-B2)") (class "Default")
      (node (ref "Q3") (pin "5") (pinfunction "B2_5") (pintype "passive"))
      (node (ref "R18") (pin "2") (pinfunction "2_2") (pintype "passive"))
    )
    (net (code "55") (name "Net-(Q4-D)") (class "Default")
      (node (ref "Q4") (pin "3") (pinfunction "D_3") (pintype "passive"))
      (node (ref "U7") (pin "2") (pinfunction "-_2") (pintype "passive"))
    )
    (net (code "56") (name "Net-(U1-*RST)") (class "Default")
      (node (ref "R1") (pin "2") (pinfunction "2_2") (pintype "passive"))
      (node (ref "U1") (pin "9") (pinfunction "*RST_9") (pintype "passive"))
    )
    (net (code "57") (name "Net-(U1-TXD)") (class "Default")
      (node (ref "R7") (pin "2") (pinfunction "2_2") (pintype "passive"))
      (node (ref "U1") (pin "26") (pinfunction "TXD_26") (pintype "passive"))
    )
    (net (code "58") (name "Net-(U2-BYPASS)") (class "Default")
      (node (ref "C4") (pin "2") (pinfunction "2_2") (pintype "passive"))
      (node (ref "U2") (pin "4") (pinfunction "BYPASS_4") (pintype "passive"))
    )
    (net (code "59") (name "Net-(U3-NSLEEP)") (class "Default")
      (node (ref "R10") (pin "1") (pinfunction "1_1") (pintype "passive"))
      (node (ref "U3") (pin "1") (pinfunction "NSLEEP_1") (pintype "bidirectional"))
    )
    (net (code "60") (name "Net-(U3-VCP)") (class "Default")
      (node (ref "C10") (pin "2") (pinfunction "2_2") (pintype "passive"))
      (node (ref "U3") (pin "11") (pinfunction "VCP_11") (pintype "bidirectional"))
    )
    (net (code "61") (name "Net-(U3-VINT)") (class "Default")
      (node (ref "C3") (pin "2") (pinfunction "2_2") (pintype "passive"))
      (node (ref "U3") (pin "14") (pinfunction "VINT_14") (pintype "input"))
    )
    (net (code "62") (name "Net-(U5-PROG)") (class "Default")
      (node (ref "R14") (pin "1") (pinfunction "1_1") (pintype "passive"))
      (node (ref "U5") (pin "5") (pinfunction "PROG_5") (pintype "passive"))
    )
    (net (code "63") (name "Net-(U6-REGOUT)") (class "Default")
      (node (ref "C17") (pin "2") (pinfunction "2_2") (pintype "passive"))
      (node (ref "U6") (pin "10") (pinfunction "REGOUT_10") (pintype "passive"))
    )
    (net (code "64") (name "Net-(USB1-CC1)") (class "Default")
      (node (ref "R20") (pin "1") (pinfunction "1_1") (pintype "passive"))
      (node (ref "USB1") (pin "A5") (pinfunction "CC1_A5") (pintype "passive"))
    )
    (net (code "65") (name "Net-(USB1-CC2)") (class "Default")
      (node (ref "R19") (pin "2") (pinfunction "2_2") (pintype "passive"))
      (node (ref "USB1") (pin "B5") (pinfunction "CC2_B5") (pintype "passive"))
    )
    (net (code "66") (name "VBAT") (class "Default")
      (node (ref "Q1") (pin "3") (pinfunction "D_3") (pintype "passive"))
      (node (ref "R2") (pin "2") (pinfunction "2_2") (pintype "passive"))
      (node (ref "R23") (pin "2") (pinfunction "2_2") (pintype "passive"))
      (node (ref "U2") (pin "1") (pinfunction "VIN_1") (pintype "passive"))
      (node (ref "U2") (pin "3") (pinfunction "ON/OFF_3") (pintype "passive"))
      (node (ref "U7") (pin "1") (pinfunction "+_1") (pintype "passive"))
    )
    (net (code "67") (name "VBAT_IN") (class "Default")
      (node (ref "C12") (pin "2") (pinfunction "2_2") (pintype "passive"))
      (node (ref "C13") (pin "2") (pinfunction "2_2") (pintype "passive"))
      (node (ref "Q1") (pin "2") (pinfunction "S_2") (pintype "passive"))
      (node (ref "R3") (pin "1") (pinfunction "1_1") (pintype "passive"))
      (node (ref "U5") (pin "3") (pinfunction "VBAT_3") (pintype "power_in"))
    )
    (net (code "68") (name "VCC_3V3") (class "Default")
      (node (ref "C1") (pin "2") (pinfunction "2_2") (pintype "passive"))
      (node (ref "C15") (pin "1") (pinfunction "1_1") (pintype "passive"))
      (node (ref "C16") (pin "1") (pinfunction "1_1") (pintype "passive"))
      (node (ref "C2") (pin "2") (pinfunction "2_2") (pintype "passive"))
      (node (ref "R11") (pin "1") (pinfunction "1_1") (pintype "passive"))
      (node (ref "R17") (pin "2") (pinfunction "2_2") (pintype "passive"))
      (node (ref "R21") (pin "1") (pinfunction "1_1") (pintype "passive"))
      (node (ref "R22") (pin "1") (pinfunction "1_1") (pintype "passive"))
      (node (ref "R24") (pin "1") (pinfunction "1_1") (pintype "passive"))
      (node (ref "U2") (pin "5") (pinfunction "VOUT_5") (pintype "passive"))
      (node (ref "U6") (pin "1") (pinfunction "RESV_1") (pintype "passive"))
      (node (ref "U6") (pin "13") (pinfunction "VDD_13") (pintype "passive"))
      (node (ref "U6") (pin "22") (pinfunction "~{CS}_22") (pintype "passive"))
      (node (ref "U6") (pin "8") (pinfunction "VDDIO_8") (pintype "passive"))
      (node (ref "U8") (pin "12") (pinfunction "VCC_12") (pintype "passive"))
      (node (ref "U9") (pin "1") (pinfunction "VCC_1") (pintype "passive"))
    )
    (net (code "69") (name "VCC_5V") (class "Default")
      (node (ref "R10") (pin "2") (pinfunction "2_2") (pintype "passive"))
      (node (ref "R12") (pin "2") (pinfunction "2_2") (pintype "passive"))
      (node (ref "R5") (pin "2") (pinfunction "2_2") (pintype "passive"))
    )
    (net (code "70") (name "VREF_2V5") (class "Default")
      (node (ref "C8") (pin "2") (pinfunction "2_2") (pintype "passive"))
      (node (ref "C9") (pin "2") (pinfunction "2_2") (pintype "passive"))
      (node (ref "R11") (pin "2") (pinfunction "2_2") (pintype "passive"))
      (node (ref "U4") (pin "1") (pinfunction "CATHODE_1") (pintype "passive"))
      (node (ref "U4") (pin "2") (pinfunction "REF_2") (pintype "passive"))
    )
    (net (code "71") (name "VUSB") (class "Default")
      (node (ref "C14") (pin "2") (pinfunction "2_2") (pintype "passive"))
      (node (ref "D4") (pin "1") (pinfunction "A_1") (pintype "passive"))
      (node (ref "R1") (pin "1") (pinfunction "1_1") (pintype "passive"))
      (node (ref "U1") (pin "7") (pinfunction "REGIN_7") (pintype "passive"))
      (node (ref "U1") (pin "8") (pinfunction "VBUS_8") (pintype "passive"))
      (node (ref "U5") (pin "4") (pinfunction "VDD_4") (pintype "power_in"))
      (node (ref "USB1") (pin "A4") (pinfunction "VBUS_A4") (pintype "passive"))
      (node (ref "USB1") (pin "A9") (pinfunction "VBUS_A9") (pintype "passive"))
      (node (ref "USB1") (pin "B4") (pinfunction "VBUS_B4") (pintype "passive"))
      (node (ref "USB1") (pin "B9") (pinfunction "VBUS_B9") (pintype "passive"))
    )
    (net (code "72") (name "unconnected-(U1-*SUSPEND-Pad11)") (class "Default")
      (node (ref "U1") (pin "11") (pinfunction "*SUSPEND_11") (pintype "passive"))
    )
    (net (code "73") (name "unconnected-(U1-CTS-Pad23)") (class "Default")
      (node (ref "U1") (pin "23") (pinfunction "CTS_23") (pintype "passive"))
    )
    (net (code "74") (name "unconnected-(U1-DCD-Pad1)") (class "Default")
      (node (ref "U1") (pin "1") (pinfunction "DCD_1") (pintype "passive"))
    )
    (net (code "75") (name "unconnected-(U1-DSR-Pad27)") (class "Default")
      (node (ref "U1") (pin "27") (pinfunction "DSR_27") (pintype "passive"))
    )
    (net (code "76") (name "unconnected-(U1-NC-Pad10)") (class "Default")
      (node (ref "U1") (pin "10") (pinfunction "NC_10") (pintype "passive"))
    )
    (net (code "77") (name "unconnected-(U1-NC-Pad13)") (class "Default")
      (node (ref "U1") (pin "13") (pinfunction "NC_13") (pintype "passive"))
    )
    (net (code "78") (name "unconnected-(U1-NC-Pad14)") (class "Default")
      (node (ref "U1") (pin "14") (pinfunction "NC_14") (pintype "passive"))
    )
    (net (code "79") (name "unconnected-(U1-NC-Pad15)") (class "Default")
      (node (ref "U1") (pin "15") (pinfunction "NC_15") (pintype "passive"))
    )
    (net (code "80") (name "unconnected-(U1-NC-Pad16)") (class "Default")
      (node (ref "U1") (pin "16") (pinfunction "NC_16") (pintype "passive"))
    )
    (net (code "81") (name "unconnected-(U1-NC-Pad17)") (class "Default")
      (node (ref "U1") (pin "17") (pinfunction "NC_17") (pintype "passive"))
    )
    (net (code "82") (name "unconnected-(U1-NC-Pad18)") (class "Default")
      (node (ref "U1") (pin "18") (pinfunction "NC_18") (pintype "passive"))
    )
    (net (code "83") (name "unconnected-(U1-NC-Pad19)") (class "Default")
      (node (ref "U1") (pin "19") (pinfunction "NC_19") (pintype "passive"))
    )
    (net (code "84") (name "unconnected-(U1-NC-Pad20)") (class "Default")
      (node (ref "U1") (pin "20") (pinfunction "NC_20") (pintype "passive"))
    )
    (net (code "85") (name "unconnected-(U1-NC-Pad21)") (class "Default")
      (node (ref "U1") (pin "21") (pinfunction "NC_21") (pintype "passive"))
    )
    (net (code "86") (name "unconnected-(U1-NC-Pad22)") (class "Default")
      (node (ref "U1") (pin "22") (pinfunction "NC_22") (pintype "passive"))
    )
    (net (code "87") (name "unconnected-(U1-RI-Pad2)") (class "Default")
      (node (ref "U1") (pin "2") (pinfunction "RI_2") (pintype "passive"))
    )
    (net (code "88") (name "unconnected-(U1-SUSPEND-Pad12)") (class "Default")
      (node (ref "U1") (pin "12") (pinfunction "SUSPEND_12") (pintype "passive"))
    )
    (net (code "89") (name "unconnected-(U1-VDD-Pad6)") (class "Default")
      (node (ref "U1") (pin "6") (pinfunction "VDD_6") (pintype "passive"))
    )
    (net (code "90") (name "unconnected-(U3-B_IN1-Pad9)") (class "Default")
      (node (ref "U3") (pin "9") (pinfunction "B_IN1_9") (pintype "input"))
    )
    (net (code "91") (name "unconnected-(U3-B_IN2-Pad10)") (class "Default")
      (node (ref "U3") (pin "10") (pinfunction "B_IN2_10") (pintype "input"))
    )
    (net (code "92") (name "unconnected-(U3-B_OUT1-Pad7)") (class "Default")
      (node (ref "U3") (pin "7") (pinfunction "B_OUT1_7") (pintype "output"))
    )
    (net (code "93") (name "unconnected-(U3-B_OUT2-Pad5)") (class "Default")
      (node (ref "U3") (pin "5") (pinfunction "B_OUT2_5") (pintype "output"))
    )
    (net (code "94") (name "unconnected-(U3-NFAULT-Pad8)") (class "Default")
      (node (ref "U3") (pin "8") (pinfunction "NFAULT_8") (pintype "bidirectional"))
    )
    (net (code "95") (name "unconnected-(U6-AUX_CL-Pad7)") (class "Default")
      (node (ref "U6") (pin "7") (pinfunction "AUX_CL_7") (pintype "passive"))
    )
    (net (code "96") (name "unconnected-(U6-AUX_DA-Pad21)") (class "Default")
      (node (ref "U6") (pin "21") (pinfunction "AUX_DA_21") (pintype "passive"))
    )
    (net (code "97") (name "unconnected-(U6-INT-Pad12)") (class "Default")
      (node (ref "U6") (pin "12") (pinfunction "INT_12") (pintype "passive"))
    )
    (net (code "98") (name "unconnected-(U6-MNT_PAD-Pad25)") (class "Default")
      (node (ref "U6") (pin "25") (pinfunction "MNT_PAD_25") (pintype "passive"))
    )
    (net (code "99") (name "unconnected-(U6-NC-Pad2)") (class "Default")
      (node (ref "U6") (pin "2") (pinfunction "NC_2") (pintype "passive"))
    )
    (net (code "100") (name "unconnected-(U6-NC-Pad3)") (class "Default")
      (node (ref "U6") (pin "3") (pinfunction "NC_3") (pintype "passive"))
    )
    (net (code "101") (name "unconnected-(U6-NC-Pad4)") (class "Default")
      (node (ref "U6") (pin "4") (pinfunction "NC_4") (pintype "passive"))
    )
    (net (code "102") (name "unconnected-(U6-NC-Pad5)") (class "Default")
      (node (ref "U6") (pin "5") (pinfunction "NC_5") (pintype "passive"))
    )
    (net (code "103") (name "unconnected-(U6-NC-Pad6)") (class "Default")
      (node (ref "U6") (pin "6") (pinfunction "NC_6") (pintype "passive"))
    )
    (net (code "104") (name "unconnected-(U6-NC-Pad14)") (class "Default")
      (node (ref "U6") (pin "14") (pinfunction "NC_14") (pintype "passive"))
    )
    (net (code "105") (name "unconnected-(U6-NC-Pad15)") (class "Default")
      (node (ref "U6") (pin "15") (pinfunction "NC_15") (pintype "passive"))
    )
    (net (code "106") (name "unconnected-(U6-NC-Pad16)") (class "Default")
      (node (ref "U6") (pin "16") (pinfunction "NC_16") (pintype "passive"))
    )
    (net (code "107") (name "unconnected-(U6-NC-Pad17)") (class "Default")
      (node (ref "U6") (pin "17") (pinfunction "NC_17") (pintype "passive"))
    )
    (net (code "108") (name "unconnected-(U6-RESV-Pad19)") (class "Default")
      (node (ref "U6") (pin "19") (pinfunction "RESV_19") (pintype "passive"))
    )
    (net (code "109") (name "unconnected-(U8-PIO0-Pad23)") (class "Default")
      (node (ref "U8") (pin "23") (pinfunction "PIO0_23") (pintype "passive"))
    )
    (net (code "110") (name "unconnected-(U8-PIO1-Pad24)") (class "Default")
      (node (ref "U8") (pin "24") (pinfunction "PIO1_24") (pintype "passive"))
    )
    (net (code "111") (name "unconnected-(U8-PIO10-Pad33)") (class "Default")
      (node (ref "U8") (pin "33") (pinfunction "PIO10_33") (pintype "passive"))
    )
    (net (code "112") (name "unconnected-(U10-CAP1_NC-Pad48)") (class "Default")
      (node (ref "U10") (pin "48") (pinfunction "CAP1_NC_48") (pintype "passive"))
    )
    (net (code "113") (name "unconnected-(U10-CAP2_NC-Pad47)") (class "Default")
      (node (ref "U10") (pin "47") (pinfunction "CAP2_NC_47") (pintype "passive"))
    )
    (net (code "114") (name "unconnected-(U10-LNA_IN-Pad2)") (class "Default")
      (node (ref "U10") (pin "2") (pinfunction "LNA_IN_2") (pintype "passive"))
    )
    (net (code "115") (name "unconnected-(U10-VDD_SDIO_NC-Pad26)") (class "Default")
      (node (ref "U10") (pin "26") (pinfunction "VDD_SDIO_NC_26") (pintype "passive"))
    )
    (net (code "116") (name "unconnected-(U10-XTAL_N_NC-Pad44)") (class "Default")
      (node (ref "U10") (pin "44") (pinfunction "XTAL_N_NC_44") (pintype "passive"))
    )
    (net (code "117") (name "unconnected-(U10-XTAL_P_NC-Pad45)") (class "Default")
      (node (ref "U10") (pin "45") (pinfunction "XTAL_P_NC_45") (pintype "passive"))
    )
    (net (code "118") (name "unconnected-(USB1-RX1+-PadB11)") (class "Default")
      (node (ref "USB1") (pin "B11") (pinfunction "RX1+_B11") (pintype "passive"))
    )
    (net (code "119") (name "unconnected-(USB1-RX1--PadB10)") (class "Default")
      (node (ref "USB1") (pin "B10") (pinfunction "RX1-_B10") (pintype "passive"))
    )
    (net (code "120") (name "unconnected-(USB1-RX2+-PadA11)") (class "Default")
      (node (ref "USB1") (pin "A11") (pinfunction "RX2+_A11") (pintype "passive"))
    )
    (net (code "121") (name "unconnected-(USB1-RX2--PadA10)") (class "Default")
      (node (ref "USB1") (pin "A10") (pinfunction "RX2-_A10") (pintype "passive"))
    )
    (net (code "122") (name "unconnected-(USB1-SBU1-PadA8)") (class "Default")
      (node (ref "USB1") (pin "A8") (pinfunction "SBU1_A8") (pintype "passive"))
    )
    (net (code "123") (name "unconnected-(USB1-SBU2-PadB8)") (class "Default")
      (node (ref "USB1") (pin "B8") (pinfunction "SBU2_B8") (pintype "passive"))
    )
    (net (code "124") (name "unconnected-(USB1-TX1+-PadA2)") (class "Default")
      (node (ref "USB1") (pin "A2") (pinfunction "TX1+_A2") (pintype "passive"))
    )
    (net (code "125") (name "unconnected-(USB1-TX1--PadA3)") (class "Default")
      (node (ref "USB1") (pin "A3") (pinfunction "TX1-_A3") (pintype "passive"))
    )
    (net (code "126") (name "unconnected-(USB1-TX2+-PadB2)") (class "Default")
      (node (ref "USB1") (pin "B2") (pinfunction "TX2+_B2") (pintype "passive"))
    )
    (net (code "127") (name "unconnected-(USB1-TX2--PadB3)") (class "Default")
      (node (ref "USB1") (pin "B3") (pinfunction "TX2-_B3") (pintype "passive"))
    )
  )
)
